# LM386_amp_mic_mod.net
KiCad netlist of a schematic drawn in EAGLE
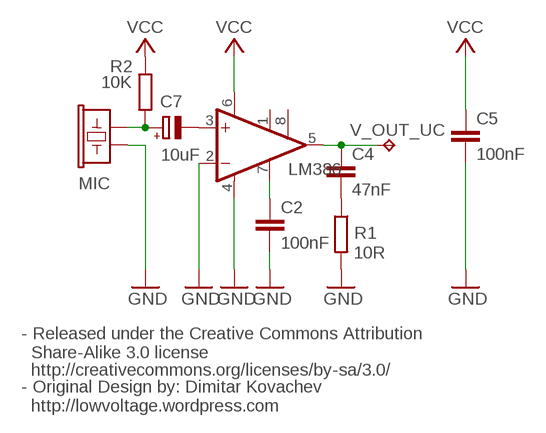
[diagram p0: schematic, sheet 1]

(export (version "E")
  (design (tool "Eeschema 10.0.6"))
  (components
    (comp (ref "C2")
      (value "100nF")
      (footprint "eagle-import:C025-030X050")
      (libsource (lib "eagle-import") (part "C-EU025-030X050"))
    )
    (comp (ref "C4")
      (value "47nF")
      (footprint "eagle-import:C025-030X050")
      (libsource (lib "eagle-import") (part "C-EU025-030X050"))
    )
    (comp (ref "C5")
      (value "100nF")
      (footprint "eagle-import:C025-025X050")
      (libsource (lib "eagle-import") (part "C-EU025-025X050"))
    )
    (comp (ref "C7")
      (value "10uF")
      (footprint "eagle-import:E2,5-6")
      (libsource (lib "eagle-import") (part "CPOL-EUE2.5-6"))
    )
    (comp (ref "LM386")
      (value "LM386N-1")
      (footprint "eagle-import:DIL08")
      (libsource (lib "eagle-import") (part "LM386?-N1"))
    )
    (comp (ref "MIC")
      (value "MIC9.7MM")
      (footprint "eagle-import:MIC-9.7MM")
      (libsource (lib "eagle-import") (part "MIC9.7MM"))
    )
    (comp (ref "R1")
      (value "10R")
      (footprint "eagle-import:0309_12")
      (libsource (lib "eagle-import") (part "R-EU_0309/12"))
    )
    (comp (ref "R2")
      (value "10K")
      (footprint "eagle-import:0309_12")
      (libsource (lib "eagle-import") (part "R-EU_0309/12"))
    )
    (comp (ref "V_OUT_UC")
      (value "TPB1,27")
      (footprint "eagle-import:B1,27")
      (libsource (lib "eagle-import") (part "TPB1,27"))
    )
  )
  (nets
    (net (code "1") (name "GND") (class "Default")
      (node (ref "C2") (pin "2") (pinfunction "2_2") (pintype "passive"))
      (node (ref "C5") (pin "2") (pinfunction "2_2") (pintype "passive"))
      (node (ref "LM386") (pin "2") (pinfunction "-IN_2") (pintype "input"))
      (node (ref "LM386") (pin "4") (pinfunction "GND_4") (pintype "power_in"))
      (node (ref "MIC") (pin "2") (pinfunction "2_2") (pintype "passive"))
      (node (ref "R1") (pin "2") (pinfunction "2_2") (pintype "passive"))
    )
    (net (code "2") (name "Net-(C4-Pad2)") (class "Default")
      (node (ref "C4") (pin "2") (pinfunction "2_2") (pintype "passive"))
      (node (ref "R1") (pin "1") (pinfunction "1_1") (pintype "passive"))
    )
    (net (code "3") (name "Net-(C7-Pad+)") (class "Default")
      (node (ref "C7") (pin "+") (pinfunction "+_+") (pintype "passive"))
      (node (ref "MIC") (pin "1") (pinfunction "1_1") (pintype "passive"))
      (node (ref "R2") (pin "2") (pinfunction "2_2") (pintype "passive"))
    )
    (net (code "4") (name "Net-(LM386-+IN)") (class "Default")
      (node (ref "C7") (pin "-") (pinfunction "-_-") (pintype "passive"))
      (node (ref "LM386") (pin "3") (pinfunction "+IN_3") (pintype "input"))
    )
    (net (code "5") (name "Net-(LM386-BYPASS)") (class "Default")
      (node (ref "C2") (pin "1") (pinfunction "1_1") (pintype "passive"))
      (node (ref "LM386") (pin "7") (pinfunction "BYPASS_7") (pintype "passive"))
    )
    (net (code "6") (name "Net-(LM386-OUT)") (class "Default")
      (node (ref "C4") (pin "1") (pinfunction "1_1") (pintype "passive"))
      (node (ref "LM386") (pin "5") (pinfunction "OUT_5") (pintype "output"))
      (node (ref "V_OUT_UC") (pin "TP") (pinfunction "TP_TP") (pintype "input"))
    )
    (net (code "7") (name "VCC") (class "Default")
      (node (ref "C5") (pin "1") (pinfunction "1_1") (pintype "passive"))
      (node (ref "LM386") (pin "6") (pinfunction "VS_6") (pintype "power_in"))
      (node (ref "R2") (pin "1") (pinfunction "1_1") (pintype "passive"))
    )
    (net (code "8") (name "unconnected-(LM386-GAIN-Pad1)") (class "Default")
      (node (ref "LM386") (pin "1") (pinfunction "GAIN_1") (pintype "passive"))
    )
    (net (code "9") (name "unconnected-(LM386-GAIN-Pad8)") (class "Default")
      (node (ref "LM386") (pin "8") (pinfunction "GAIN_8") (pintype "passive"))
    )
  )
)
